# v0_2.net
KiCad netlist of a schematic drawn in EAGLE
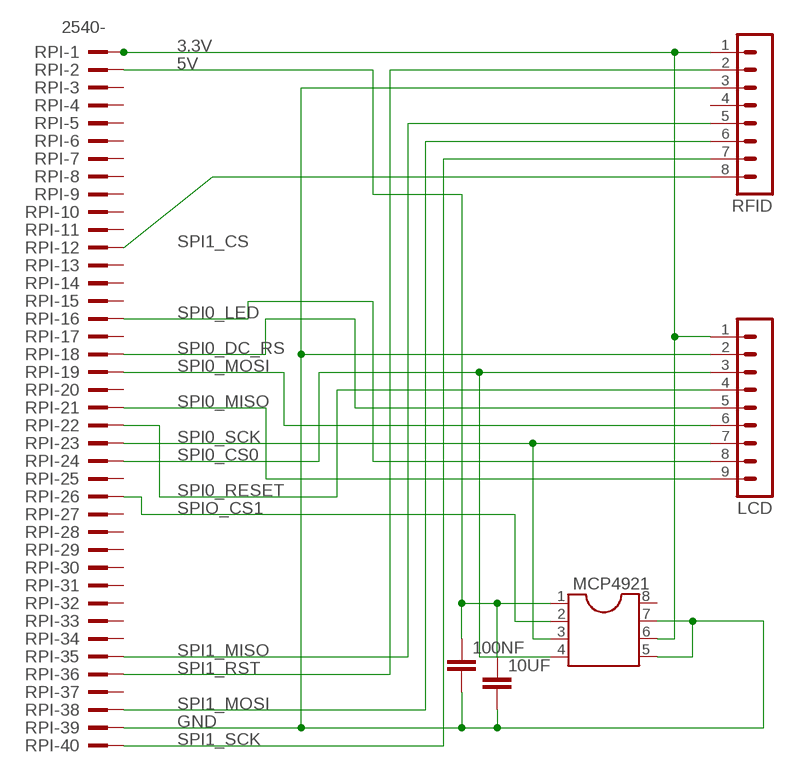
[diagram p0: schematic, sheet 1]

(export (version "E")
  (design (tool "Eeschema 10.0.6"))
  (components
    (comp (ref "10UF")
      (value "C-EU025-025X050")
      (footprint "eagle-import:C025-025X050")
      (libsource (lib "eagle-import") (part "C-EU025-025X050"))
    )
    (comp (ref "100NF")
      (value "C-EU025-025X050")
      (footprint "eagle-import:C025-025X050")
      (libsource (lib "eagle-import") (part "C-EU025-025X050"))
    )
    (comp (ref "LCD")
      (value "MA09-1")
      (footprint "eagle-import:MA09-1")
      (libsource (lib "eagle-import") (part "MA09-1"))
    )
    (comp (ref "MCP4921")
      (value "DIL8")
      (footprint "eagle-import:DIL08")
      (libsource (lib "eagle-import") (part "DIL8"))
    )
    (comp (ref "RFID")
      (value "MA08-1")
      (footprint "eagle-import:MA08-1")
      (libsource (lib "eagle-import") (part "MA08-1"))
    )
    (comp (ref "RPI")
      (value "2540-")
      (footprint "eagle-import:PAK100_2500-40")
      (libsource (lib "eagle-import") (part "2540-"))
    )
  )
  (nets
    (net (code "1") (name "/3.3V") (class "Default")
      (node (ref "LCD") (pin "1") (pinfunction "1_1") (pintype "passive"))
      (node (ref "MCP4921") (pin "6") (pinfunction "6_6") (pintype "passive"))
      (node (ref "RFID") (pin "1") (pinfunction "1_1") (pintype "passive"))
      (node (ref "RPI") (pin "1") (pinfunction "KL_1") (pintype "passive"))
    )
    (net (code "2") (name "/5V") (class "Default")
      (node (ref "100NF") (pin "1") (pinfunction "1_1") (pintype "passive"))
      (node (ref "10UF") (pin "1") (pinfunction "1_1") (pintype "passive"))
      (node (ref "MCP4921") (pin "1") (pinfunction "1_1") (pintype "passive"))
      (node (ref "RPI") (pin "2") (pinfunction "KL_2") (pintype "passive"))
    )
    (net (code "3") (name "/GND") (class "Default")
      (node (ref "100NF") (pin "2") (pinfunction "2_2") (pintype "passive"))
      (node (ref "10UF") (pin "2") (pinfunction "2_2") (pintype "passive"))
      (node (ref "LCD") (pin "2") (pinfunction "2_2") (pintype "passive"))
      (node (ref "MCP4921") (pin "5") (pinfunction "5_5") (pintype "passive"))
      (node (ref "MCP4921") (pin "7") (pinfunction "7_7") (pintype "passive"))
      (node (ref "RFID") (pin "3") (pinfunction "3_3") (pintype "passive"))
      (node (ref "RPI") (pin "39") (pinfunction "KL_39") (pintype "passive"))
    )
    (net (code "4") (name "/SPI0_CS0") (class "Default")
      (node (ref "LCD") (pin "3") (pinfunction "3_3") (pintype "passive"))
      (node (ref "MCP4921") (pin "4") (pinfunction "4_4") (pintype "passive"))
      (node (ref "RPI") (pin "24") (pinfunction "KL_24") (pintype "passive"))
    )
    (net (code "5") (name "/SPI0_DC_RS") (class "Default")
      (node (ref "LCD") (pin "5") (pinfunction "5_5") (pintype "passive"))
      (node (ref "RPI") (pin "18") (pinfunction "KL_18") (pintype "passive"))
    )
    (net (code "6") (name "/SPI0_LED") (class "Default")
      (node (ref "LCD") (pin "8") (pinfunction "8_8") (pintype "passive"))
      (node (ref "RPI") (pin "16") (pinfunction "KL_16") (pintype "passive"))
    )
    (net (code "7") (name "/SPI0_MISO") (class "Default")
      (node (ref "LCD") (pin "9") (pinfunction "9_9") (pintype "passive"))
      (node (ref "RPI") (pin "21") (pinfunction "KL_21") (pintype "passive"))
    )
    (net (code "8") (name "/SPI0_MOSI") (class "Default")
      (node (ref "LCD") (pin "6") (pinfunction "6_6") (pintype "passive"))
      (node (ref "RPI") (pin "19") (pinfunction "KL_19") (pintype "passive"))
    )
    (net (code "9") (name "/SPI0_RESET") (class "Default")
      (node (ref "LCD") (pin "4") (pinfunction "4_4") (pintype "passive"))
      (node (ref "RPI") (pin "22") (pinfunction "KL_22") (pintype "passive"))
    )
    (net (code "10") (name "/SPI0_SCK") (class "Default")
      (node (ref "LCD") (pin "7") (pinfunction "7_7") (pintype "passive"))
      (node (ref "MCP4921") (pin "3") (pinfunction "3_3") (pintype "passive"))
      (node (ref "RPI") (pin "23") (pinfunction "KL_23") (pintype "passive"))
    )
    (net (code "11") (name "/SPI1_CS") (class "Default")
      (node (ref "RFID") (pin "8") (pinfunction "8_8") (pintype "passive"))
      (node (ref "RPI") (pin "12") (pinfunction "KL_12") (pintype "passive"))
    )
    (net (code "12") (name "/SPI1_MISO") (class "Default")
      (node (ref "RFID") (pin "5") (pinfunction "5_5") (pintype "passive"))
      (node (ref "RPI") (pin "35") (pinfunction "KL_35") (pintype "passive"))
    )
    (net (code "13") (name "/SPI1_MOSI") (class "Default")
      (node (ref "RFID") (pin "6") (pinfunction "6_6") (pintype "passive"))
      (node (ref "RPI") (pin "38") (pinfunction "KL_38") (pintype "passive"))
    )
    (net (code "14") (name "/SPI1_RST") (class "Default")
      (node (ref "RFID") (pin "2") (pinfunction "2_2") (pintype "passive"))
      (node (ref "RPI") (pin "36") (pinfunction "KL_36") (pintype "passive"))
    )
    (net (code "15") (name "/SPI1_SCK") (class "Default")
      (node (ref "RFID") (pin "7") (pinfunction "7_7") (pintype "passive"))
      (node (ref "RPI") (pin "40") (pinfunction "KL_40") (pintype "passive"))
    )
    (net (code "16") (name "/SPIO_CS1") (class "Default")
      (node (ref "MCP4921") (pin "2") (pinfunction "2_2") (pintype "passive"))
      (node (ref "RPI") (pin "26") (pinfunction "KL_26") (pintype "passive"))
    )
    (net (code "17") (name "unconnected-(MCP4921-Pad8)") (class "Default")
      (node (ref "MCP4921") (pin "8") (pinfunction "8_8") (pintype "passive"))
    )
    (net (code "18") (name "unconnected-(RFID-Pad4)") (class "Default")
      (node (ref "RFID") (pin "4") (pinfunction "4_4") (pintype "passive"))
    )
    (net (code "19") (name "unconnected-(RPIAA-KL-Pad33)") (class "Default")
      (node (ref "RPI") (pin "33") (pinfunction "KL_33") (pintype "passive"))
    )
    (net (code "20") (name "unconnected-(RPIAB-KL-Pad34)") (class "Default")
      (node (ref "RPI") (pin "34") (pinfunction "KL_34") (pintype "passive"))
    )
    (net (code "21") (name "unconnected-(RPIAE-KL-Pad37)") (class "Default")
      (node (ref "RPI") (pin "37") (pinfunction "KL_37") (pintype "passive"))
    )
    (net (code "22") (name "unconnected-(RPIAH-KL-Pad4)") (class "Default")
      (node (ref "RPI") (pin "4") (pinfunction "KL_4") (pintype "passive"))
    )
    (net (code "23") (name "unconnected-(RPIAJ-KL-Pad5)") (class "Default")
      (node (ref "RPI") (pin "5") (pinfunction "KL_5") (pintype "passive"))
    )
    (net (code "24") (name "unconnected-(RPIAK-KL-Pad6)") (class "Default")
      (node (ref "RPI") (pin "6") (pinfunction "KL_6") (pintype "passive"))
    )
    (net (code "25") (name "unconnected-(RPIAL-KL-Pad7)") (class "Default")
      (node (ref "RPI") (pin "7") (pinfunction "KL_7") (pintype "passive"))
    )
    (net (code "26") (name "unconnected-(RPIAM-KL-Pad8)") (class "Default")
      (node (ref "RPI") (pin "8") (pinfunction "KL_8") (pintype "passive"))
    )
    (net (code "27") (name "unconnected-(RPIAN-KL-Pad9)") (class "Default")
      (node (ref "RPI") (pin "9") (pinfunction "KL_9") (pintype "passive"))
    )
    (net (code "28") (name "unconnected-(RPIB-KL-Pad10)") (class "Default")
      (node (ref "RPI") (pin "10") (pinfunction "KL_10") (pintype "passive"))
    )
    (net (code "29") (name "unconnected-(RPIC-KL-Pad11)") (class "Default")
      (node (ref "RPI") (pin "11") (pinfunction "KL_11") (pintype "passive"))
    )
    (net (code "30") (name "unconnected-(RPIE-KL-Pad13)") (class "Default")
      (node (ref "RPI") (pin "13") (pinfunction "KL_13") (pintype "passive"))
    )
    (net (code "31") (name "unconnected-(RPIF-KL-Pad14)") (class "Default")
      (node (ref "RPI") (pin "14") (pinfunction "KL_14") (pintype "passive"))
    )
    (net (code "32") (name "unconnected-(RPIG-KL-Pad15)") (class "Default")
      (node (ref "RPI") (pin "15") (pinfunction "KL_15") (pintype "passive"))
    )
    (net (code "33") (name "unconnected-(RPII-KL-Pad17)") (class "Default")
      (node (ref "RPI") (pin "17") (pinfunction "KL_17") (pintype "passive"))
    )
    (net (code "34") (name "unconnected-(RPIM-KL-Pad20)") (class "Default")
      (node (ref "RPI") (pin "20") (pinfunction "KL_20") (pintype "passive"))
    )
    (net (code "35") (name "unconnected-(RPIR-KL-Pad25)") (class "Default")
      (node (ref "RPI") (pin "25") (pinfunction "KL_25") (pintype "passive"))
    )
    (net (code "36") (name "unconnected-(RPIT-KL-Pad27)") (class "Default")
      (node (ref "RPI") (pin "27") (pinfunction "KL_27") (pintype "passive"))
    )
    (net (code "37") (name "unconnected-(RPIU-KL-Pad28)") (class "Default")
      (node (ref "RPI") (pin "28") (pinfunction "KL_28") (pintype "passive"))
    )
    (net (code "38") (name "unconnected-(RPIV-KL-Pad29)") (class "Default")
      (node (ref "RPI") (pin "29") (pinfunction "KL_29") (pintype "passive"))
    )
    (net (code "39") (name "unconnected-(RPIW-KL-Pad3)") (class "Default")
      (node (ref "RPI") (pin "3") (pinfunction "KL_3") (pintype "passive"))
    )
    (net (code "40") (name "unconnected-(RPIX-KL-Pad30)") (class "Default")
      (node (ref "RPI") (pin "30") (pinfunction "KL_30") (pintype "passive"))
    )
    (net (code "41") (name "unconnected-(RPIY-KL-Pad31)") (class "Default")
      (node (ref "RPI") (pin "31") (pinfunction "KL_31") (pintype "passive"))
    )
    (net (code "42") (name "unconnected-(RPIZ-KL-Pad32)") (class "Default")
      (node (ref "RPI") (pin "32") (pinfunction "KL_32") (pintype "passive"))
    )
  )
)
